# Remotuino-v2.net
KiCad netlist of a schematic drawn in EAGLE
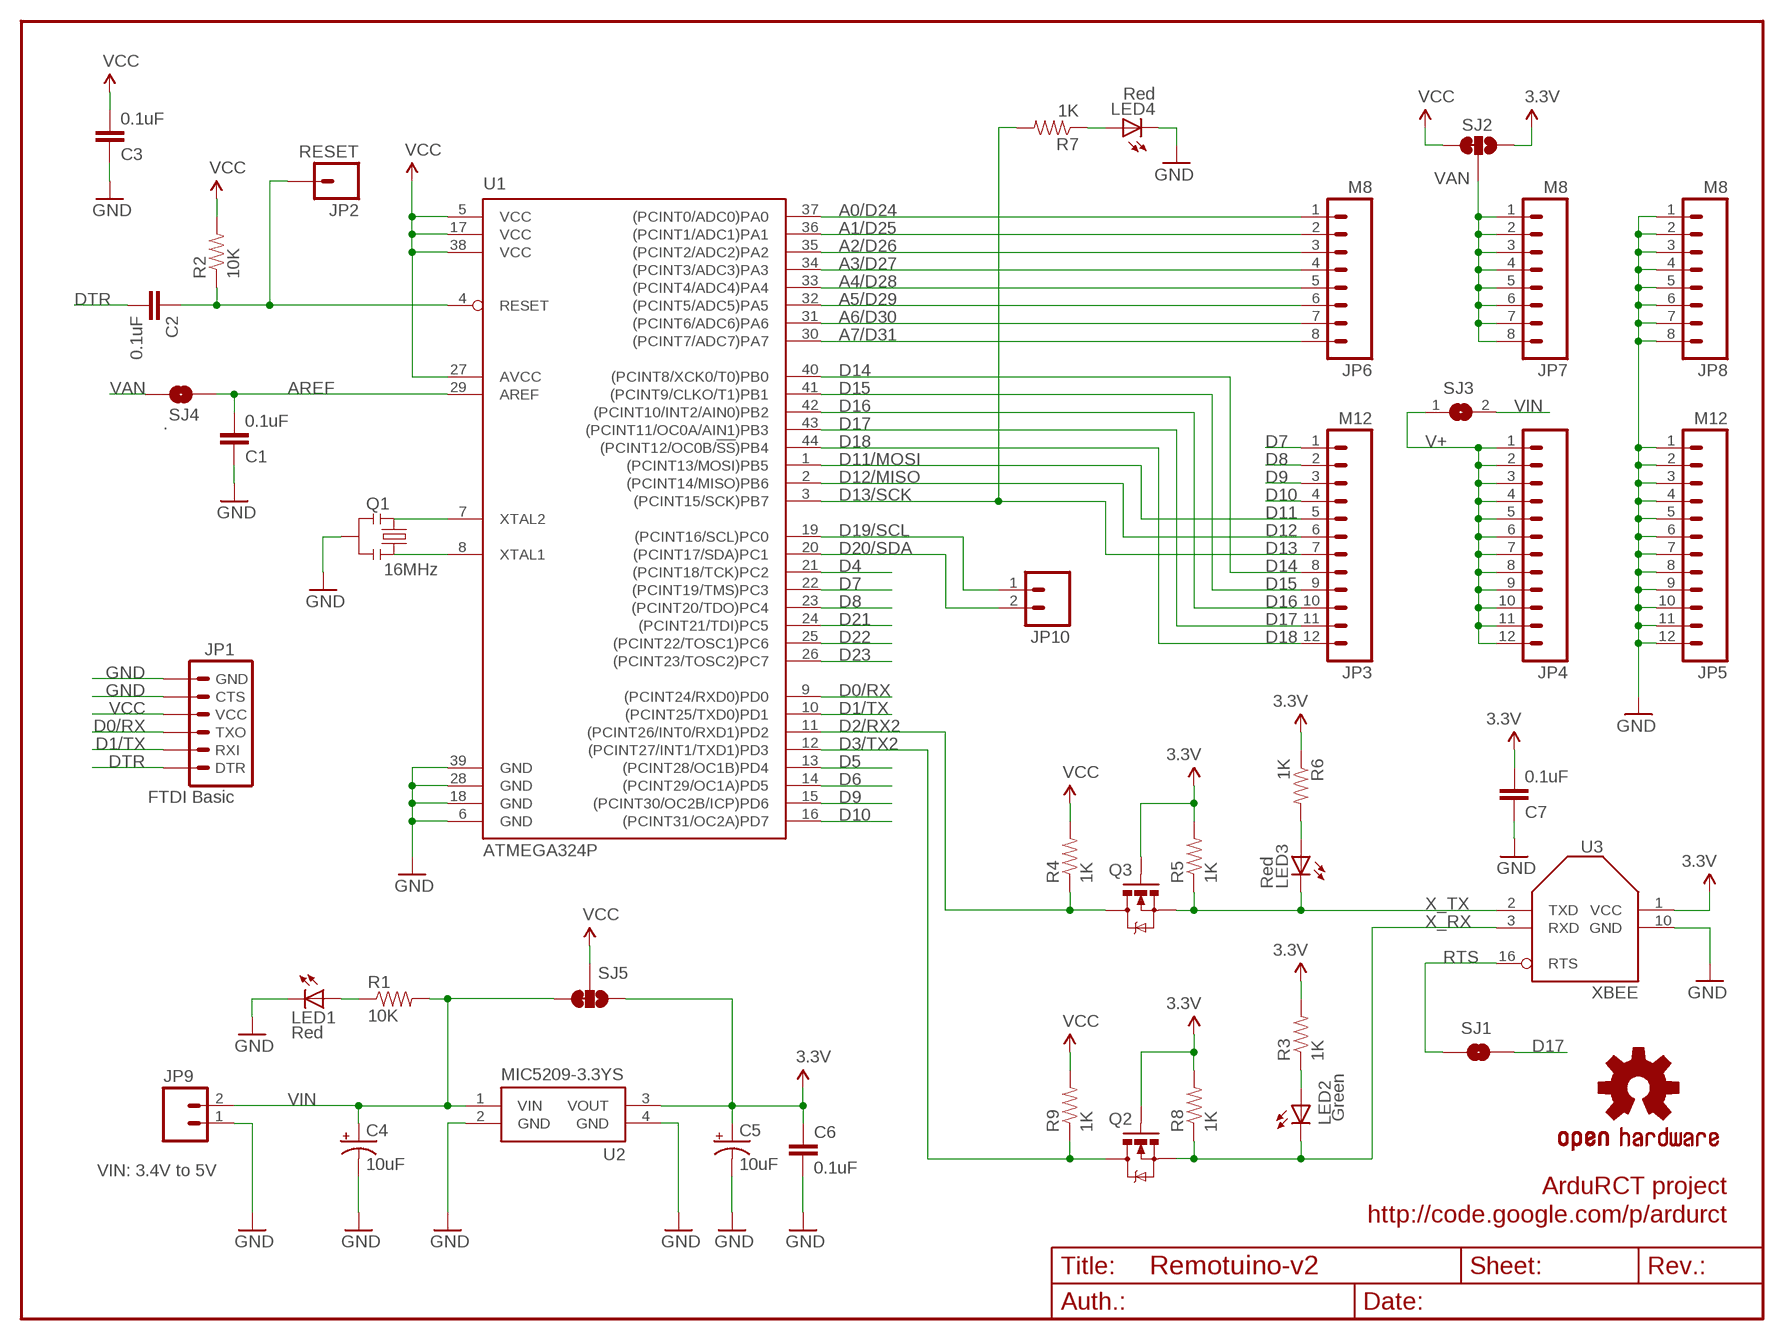
[diagram p0: schematic, sheet 1]

(export (version "E")
  (design (tool "Eeschema 10.0.6"))
  (components
    (comp (ref "C1")
      (value "0.1uF")
      (footprint "eagle-import:0805")
      (libsource (lib "eagle-import") (part "CAP0805"))
    )
    (comp (ref "C2")
      (value "0.1uF")
      (footprint "eagle-import:0805")
      (libsource (lib "eagle-import") (part "CAP0805"))
    )
    (comp (ref "C3")
      (value "0.1uF")
      (footprint "eagle-import:0805")
      (libsource (lib "eagle-import") (part "CAP0805"))
    )
    (comp (ref "C4")
      (value "10uF")
      (footprint "eagle-import:EIA3216")
      (libsource (lib "eagle-import") (part "CAP_POL1206"))
    )
    (comp (ref "C5")
      (value "10uF")
      (footprint "eagle-import:EIA3216")
      (libsource (lib "eagle-import") (part "CAP_POL1206"))
    )
    (comp (ref "C6")
      (value "0.1uF")
      (footprint "eagle-import:0805")
      (libsource (lib "eagle-import") (part "CAP0805"))
    )
    (comp (ref "C7")
      (value "0.1uF")
      (footprint "eagle-import:0805")
      (libsource (lib "eagle-import") (part "CAP0805"))
    )
    (comp (ref "JP1")
      (value "FTDI Basic")
      (footprint "eagle-import:1X06")
      (libsource (lib "eagle-import") (part "ARDUINO_SERIAL_PROGRAMPTH"))
    )
    (comp (ref "JP2")
      (value "RESET")
      (footprint "eagle-import:1X01")
      (libsource (lib "eagle-import") (part "M01PTH"))
    )
    (comp (ref "JP3")
      (value "M12")
      (footprint "eagle-import:1X12")
      (libsource (lib "eagle-import") (part "M12PTH"))
    )
    (comp (ref "JP4")
      (value "M12PTH")
      (footprint "eagle-import:1X12")
      (libsource (lib "eagle-import") (part "M12PTH"))
    )
    (comp (ref "JP5")
      (value "M12")
      (footprint "eagle-import:1X12")
      (libsource (lib "eagle-import") (part "M12PTH"))
    )
    (comp (ref "JP6")
      (value "M8")
      (footprint "eagle-import:1X08")
      (libsource (lib "eagle-import") (part "M08"))
    )
    (comp (ref "JP7")
      (value "M8")
      (footprint "eagle-import:1X08")
      (libsource (lib "eagle-import") (part "M08"))
    )
    (comp (ref "JP8")
      (value "M8")
      (footprint "eagle-import:1X08")
      (libsource (lib "eagle-import") (part "M08"))
    )
    (comp (ref "JP9")
      (value "M02L")
      (footprint "eagle-import:1X2_LONGPAD")
      (libsource (lib "eagle-import") (part "M02L"))
    )
    (comp (ref "JP10")
      (value "M02")
      (footprint "eagle-import:1X02")
      (libsource (lib "eagle-import") (part "M02"))
    )
    (comp (ref "LED1")
      (value "Red")
      (footprint "eagle-import:LED-0805")
      (libsource (lib "eagle-import") (part "LED805"))
    )
    (comp (ref "LED2")
      (value "Green")
      (footprint "eagle-import:LED-0805")
      (libsource (lib "eagle-import") (part "LED805"))
    )
    (comp (ref "LED3")
      (value "Red")
      (footprint "eagle-import:LED-0805")
      (libsource (lib "eagle-import") (part "LED805"))
    )
    (comp (ref "LED4")
      (value "Red")
      (footprint "eagle-import:LED-0805")
      (libsource (lib "eagle-import") (part "LED805"))
    )
    (comp (ref "Q1")
      (value "16MHz")
      (footprint "eagle-import:RESONATOR-SMD")
      (libsource (lib "eagle-import") (part "RESONATORSMD"))
    )
    (comp (ref "Q2")
      (value "BSS138")
      (footprint "eagle-import:SOT23-3")
      (libsource (lib "eagle-import") (part "MOSFET-NCHANNELSMD"))
    )
    (comp (ref "Q3")
      (value "BSS138")
      (footprint "eagle-import:SOT23-3")
      (libsource (lib "eagle-import") (part "MOSFET-NCHANNELSMD"))
    )
    (comp (ref "R1")
      (value "10K")
      (footprint "eagle-import:0805")
      (libsource (lib "eagle-import") (part "RESISTOR0805-RES"))
    )
    (comp (ref "R2")
      (value "10K")
      (footprint "eagle-import:0805")
      (libsource (lib "eagle-import") (part "RESISTOR0805-RES"))
    )
    (comp (ref "R3")
      (value "1K")
      (footprint "eagle-import:0805")
      (libsource (lib "eagle-import") (part "RESISTOR0805-RES"))
    )
    (comp (ref "R4")
      (value "1K")
      (footprint "eagle-import:0805")
      (libsource (lib "eagle-import") (part "RESISTOR0805-RES"))
    )
    (comp (ref "R5")
      (value "1K")
      (footprint "eagle-import:0805")
      (libsource (lib "eagle-import") (part "RESISTOR0805-RES"))
    )
    (comp (ref "R6")
      (value "1K")
      (footprint "eagle-import:0805")
      (libsource (lib "eagle-import") (part "RESISTOR0805-RES"))
    )
    (comp (ref "R7")
      (value "1K")
      (footprint "eagle-import:0805")
      (libsource (lib "eagle-import") (part "RESISTOR0805-RES"))
    )
    (comp (ref "R8")
      (value "1K")
      (footprint "eagle-import:0805")
      (libsource (lib "eagle-import") (part "RESISTOR0805-RES"))
    )
    (comp (ref "R9")
      (value "1K")
      (footprint "eagle-import:0805")
      (libsource (lib "eagle-import") (part "RESISTOR0805-RES"))
    )
    (comp (ref "SJ1")
      (value "SOLDERJUMPERNO")
      (footprint "eagle-import:SJ_2S-NO")
      (libsource (lib "eagle-import") (part "SOLDERJUMPERNO"))
    )
    (comp (ref "SJ2")
      (value "SJ_2WAYS_1-2W")
      (footprint "eagle-import:SJ_2WAYS_1-2")
      (libsource (lib "eagle-import") (part "SJ_2WAYS_1-2W"))
    )
    (comp (ref "SJ3") (value "SJ") (footprint "eagle-import:SJ") (libsource (lib "eagle-import") (part "SJ")))
    (comp (ref "SJ4")
      (value ".")
      (footprint "eagle-import:SJ_2S-TRACE")
      (libsource (lib "eagle-import") (part "SOLDERJUMPERTRACE"))
    )
    (comp (ref "SJ5")
      (value "SJ_2WAYS_1-2W")
      (footprint "eagle-import:SJ_2WAYS_1-2")
      (libsource (lib "eagle-import") (part "SJ_2WAYS_1-2W"))
    )
    (comp (ref "U$2")
      (value "OSHW-LOGOS")
      (footprint "eagle-import:OSHW-LOGO-S")
      (libsource (lib "eagle-import") (part "OSHW-LOGOS"))
    )
    (comp (ref "U1")
      (value "ATMEGA324P")
      (footprint "eagle-import:TQFP44")
      (libsource (lib "eagle-import") (part "ATMEGA324A"))
    )
    (comp (ref "U2")
      (value "MIC5209-3.3YS")
      (footprint "eagle-import:SOT223")
      (libsource (lib "eagle-import") (part "MIC5209"))
    )
    (comp (ref "U3")
      (value "XBEE")
      (footprint "eagle-import:XBEE-MIN")
      (libsource (lib "eagle-import") (part "XBEE-SIMPLE"))
    )
  )
  (nets
    (net (code "1") (name "/A0{slash}D24") (class "Default")
      (node (ref "JP6") (pin "1") (pinfunction "1_1") (pintype "passive"))
      (node (ref "U1") (pin "37") (pinfunction "(PCINT0/ADC0)PA0_37") (pintype "bidirectional"))
    )
    (net (code "2") (name "/A1{slash}D25") (class "Default")
      (node (ref "JP6") (pin "2") (pinfunction "2_2") (pintype "passive"))
      (node (ref "U1") (pin "36") (pinfunction "(PCINT1/ADC1)PA1_36") (pintype "bidirectional"))
    )
    (net (code "3") (name "/A2{slash}D26") (class "Default")
      (node (ref "JP6") (pin "3") (pinfunction "3_3") (pintype "passive"))
      (node (ref "U1") (pin "35") (pinfunction "(PCINT2/ADC2)PA2_35") (pintype "bidirectional"))
    )
    (net (code "4") (name "/A3{slash}D27") (class "Default")
      (node (ref "JP6") (pin "4") (pinfunction "4_4") (pintype "passive"))
      (node (ref "U1") (pin "34") (pinfunction "(PCINT3/ADC3)PA3_34") (pintype "bidirectional"))
    )
    (net (code "5") (name "/A4{slash}D28") (class "Default")
      (node (ref "JP6") (pin "5") (pinfunction "5_5") (pintype "passive"))
      (node (ref "U1") (pin "33") (pinfunction "(PCINT4/ADC4)PA4_33") (pintype "bidirectional"))
    )
    (net (code "6") (name "/A5{slash}D29") (class "Default")
      (node (ref "JP6") (pin "6") (pinfunction "6_6") (pintype "passive"))
      (node (ref "U1") (pin "32") (pinfunction "(PCINT5/ADC5)PA5_32") (pintype "bidirectional"))
    )
    (net (code "7") (name "/A6{slash}D30") (class "Default")
      (node (ref "JP6") (pin "7") (pinfunction "7_7") (pintype "passive"))
      (node (ref "U1") (pin "31") (pinfunction "(PCINT6/ADC6)PA6_31") (pintype "bidirectional"))
    )
    (net (code "8") (name "/A7{slash}D31") (class "Default")
      (node (ref "JP6") (pin "8") (pinfunction "8_8") (pintype "passive"))
      (node (ref "U1") (pin "30") (pinfunction "(PCINT7/ADC7)PA7_30") (pintype "bidirectional"))
    )
    (net (code "9") (name "/AREF") (class "Default")
      (node (ref "C1") (pin "2") (pinfunction "2_2") (pintype "passive"))
      (node (ref "SJ4") (pin "2") (pinfunction "2_2") (pintype "passive"))
      (node (ref "U1") (pin "29") (pinfunction "AREF_29") (pintype "passive"))
    )
    (net (code "10") (name "/D0{slash}RX") (class "Default")
      (node (ref "JP1") (pin "3") (pinfunction "TXO_3") (pintype "passive"))
      (node (ref "U1") (pin "9") (pinfunction "(PCINT24/RXD0)PD0_9") (pintype "bidirectional"))
    )
    (net (code "11") (name "/D1{slash}TX") (class "Default")
      (node (ref "JP1") (pin "2") (pinfunction "RXI_2") (pintype "passive"))
      (node (ref "U1") (pin "10") (pinfunction "(PCINT25/TXD0)PD1_10") (pintype "bidirectional"))
    )
    (net (code "12") (name "/D2{slash}RX2") (class "Default")
      (node (ref "Q3") (pin "3") (pinfunction "D_3") (pintype "passive"))
      (node (ref "R4") (pin "1") (pinfunction "1_1") (pintype "passive"))
      (node (ref "U1") (pin "11") (pinfunction "(PCINT26/INT0/RXD1)PD2_11") (pintype "bidirectional"))
    )
    (net (code "13") (name "/D3{slash}TX2") (class "Default")
      (node (ref "Q2") (pin "3") (pinfunction "D_3") (pintype "passive"))
      (node (ref "R9") (pin "1") (pinfunction "1_1") (pintype "passive"))
      (node (ref "U1") (pin "12") (pinfunction "(PCINT27/INT1/TXD1)PD3_12") (pintype "bidirectional"))
    )
    (net (code "14") (name "/D4") (class "Default")
      (node (ref "U1") (pin "21") (pinfunction "(PCINT18/TCK)PC2_21") (pintype "output"))
    )
    (net (code "15") (name "/D5") (class "Default")
      (node (ref "U1") (pin "13") (pinfunction "(PCINT28/OC1B)PD4_13") (pintype "bidirectional"))
    )
    (net (code "16") (name "/D6") (class "Default")
      (node (ref "U1") (pin "14") (pinfunction "(PCINT29/OC1A)PD5_14") (pintype "bidirectional"))
    )
    (net (code "17") (name "/D7") (class "Default")
      (node (ref "JP3") (pin "1") (pinfunction "1_1") (pintype "passive"))
      (node (ref "U1") (pin "22") (pinfunction "(PCINT19/TMS)PC3_22") (pintype "output"))
    )
    (net (code "18") (name "/D8") (class "Default")
      (node (ref "JP3") (pin "2") (pinfunction "2_2") (pintype "passive"))
      (node (ref "U1") (pin "23") (pinfunction "(PCINT20/TDO)PC4_23") (pintype "output"))
    )
    (net (code "19") (name "/D9") (class "Default")
      (node (ref "JP3") (pin "3") (pinfunction "3_3") (pintype "passive"))
      (node (ref "U1") (pin "15") (pinfunction "(PCINT30/OC2B/ICP)PD6_15") (pintype "bidirectional"))
    )
    (net (code "20") (name "/D10") (class "Default")
      (node (ref "JP3") (pin "4") (pinfunction "4_4") (pintype "passive"))
      (node (ref "U1") (pin "16") (pinfunction "(PCINT31/OC2A)PD7_16") (pintype "bidirectional"))
    )
    (net (code "21") (name "/D11{slash}MOSI") (class "Default")
      (node (ref "JP3") (pin "5") (pinfunction "5_5") (pintype "passive"))
      (node (ref "U1") (pin "1") (pinfunction "(PCINT13/MOSI)PB5_1") (pintype "bidirectional"))
    )
    (net (code "22") (name "/D12{slash}MISO") (class "Default")
      (node (ref "JP3") (pin "6") (pinfunction "6_6") (pintype "passive"))
      (node (ref "U1") (pin "2") (pinfunction "(PCINT14/MISO)PB6_2") (pintype "bidirectional"))
    )
    (net (code "23") (name "/D13{slash}SCK") (class "Default")
      (node (ref "JP3") (pin "7") (pinfunction "7_7") (pintype "passive"))
      (node (ref "R7") (pin "2") (pinfunction "2_2") (pintype "passive"))
      (node (ref "U1") (pin "3") (pinfunction "(PCINT15/SCK)PB7_3") (pintype "bidirectional"))
    )
    (net (code "24") (name "/D14") (class "Default")
      (node (ref "JP3") (pin "8") (pinfunction "8_8") (pintype "passive"))
      (node (ref "U1") (pin "40") (pinfunction "(PCINT8/XCK0/T0)PB0_40") (pintype "bidirectional"))
    )
    (net (code "25") (name "/D15") (class "Default")
      (node (ref "JP3") (pin "9") (pinfunction "9_9") (pintype "passive"))
      (node (ref "U1") (pin "41") (pinfunction "(PCINT9/CLKO/T1)PB1_41") (pintype "bidirectional"))
    )
    (net (code "26") (name "/D16") (class "Default")
      (node (ref "JP3") (pin "10") (pinfunction "10_10") (pintype "passive"))
      (node (ref "U1") (pin "42") (pinfunction "(PCINT10/INT2/AIN0)PB2_42") (pintype "bidirectional"))
    )
    (net (code "27") (name "/D17") (class "Default")
      (node (ref "JP3") (pin "11") (pinfunction "11_11") (pintype "passive"))
      (node (ref "SJ1") (pin "2") (pinfunction "2_2") (pintype "passive"))
      (node (ref "U1") (pin "43") (pinfunction "(PCINT11/OC0A/AIN1)PB3_43") (pintype "bidirectional"))
    )
    (net (code "28") (name "/D18") (class "Default")
      (node (ref "JP3") (pin "12") (pinfunction "12_12") (pintype "passive"))
      (node (ref "U1") (pin "44") (pinfunction "(PCINT12/OC0B/~{SS})PB4_44") (pintype "bidirectional"))
    )
    (net (code "29") (name "/D19{slash}SCL") (class "Default")
      (node (ref "JP10") (pin "1") (pinfunction "1_1") (pintype "passive"))
      (node (ref "U1") (pin "19") (pinfunction "(PCINT16/SCL)PC0_19") (pintype "output"))
    )
    (net (code "30") (name "/D20{slash}SDA") (class "Default")
      (node (ref "JP10") (pin "2") (pinfunction "2_2") (pintype "passive"))
      (node (ref "U1") (pin "20") (pinfunction "(PCINT17/SDA)PC1_20") (pintype "output"))
    )
    (net (code "31") (name "/D21") (class "Default")
      (node (ref "U1") (pin "24") (pinfunction "(PCINT21/TDI)PC5_24") (pintype "output"))
    )
    (net (code "32") (name "/D22") (class "Default")
      (node (ref "U1") (pin "25") (pinfunction "(PCINT22/TOSC1)PC6_25") (pintype "output"))
    )
    (net (code "33") (name "/D23") (class "Default")
      (node (ref "U1") (pin "26") (pinfunction "(PCINT23/TOSC2)PC7_26") (pintype "output"))
    )
    (net (code "34") (name "/DTR") (class "Default")
      (node (ref "C2") (pin "2") (pinfunction "2_2") (pintype "passive"))
      (node (ref "JP1") (pin "1") (pinfunction "DTR_1") (pintype "passive"))
    )
    (net (code "35") (name "/RTS") (class "Default")
      (node (ref "SJ1") (pin "1") (pinfunction "1_1") (pintype "passive"))
      (node (ref "U3") (pin "16") (pinfunction "RTS_16") (pintype "bidirectional"))
    )
    (net (code "36") (name "/V+") (class "Default")
      (node (ref "JP4") (pin "1") (pinfunction "1_1") (pintype "passive"))
      (node (ref "JP4") (pin "10") (pinfunction "10_10") (pintype "passive"))
      (node (ref "JP4") (pin "11") (pinfunction "11_11") (pintype "passive"))
      (node (ref "JP4") (pin "12") (pinfunction "12_12") (pintype "passive"))
      (node (ref "JP4") (pin "2") (pinfunction "2_2") (pintype "passive"))
      (node (ref "JP4") (pin "3") (pinfunction "3_3") (pintype "passive"))
      (node (ref "JP4") (pin "4") (pinfunction "4_4") (pintype "passive"))
      (node (ref "JP4") (pin "5") (pinfunction "5_5") (pintype "passive"))
      (node (ref "JP4") (pin "6") (pinfunction "6_6") (pintype "passive"))
      (node (ref "JP4") (pin "7") (pinfunction "7_7") (pintype "passive"))
      (node (ref "JP4") (pin "8") (pinfunction "8_8") (pintype "passive"))
      (node (ref "JP4") (pin "9") (pinfunction "9_9") (pintype "passive"))
      (node (ref "SJ3") (pin "1") (pinfunction "1_1") (pintype "passive"))
    )
    (net (code "37") (name "/VAN") (class "Default")
      (node (ref "JP7") (pin "1") (pinfunction "1_1") (pintype "passive"))
      (node (ref "JP7") (pin "2") (pinfunction "2_2") (pintype "passive"))
      (node (ref "JP7") (pin "3") (pinfunction "3_3") (pintype "passive"))
      (node (ref "JP7") (pin "4") (pinfunction "4_4") (pintype "passive"))
      (node (ref "JP7") (pin "5") (pinfunction "5_5") (pintype "passive"))
      (node (ref "JP7") (pin "6") (pinfunction "6_6") (pintype "passive"))
      (node (ref "JP7") (pin "7") (pinfunction "7_7") (pintype "passive"))
      (node (ref "JP7") (pin "8") (pinfunction "8_8") (pintype "passive"))
      (node (ref "SJ2") (pin "2") (pinfunction "2_2") (pintype "passive"))
      (node (ref "SJ4") (pin "1") (pinfunction "1_1") (pintype "passive"))
    )
    (net (code "38") (name "/VIN") (class "Default")
      (node (ref "C4") (pin "A") (pinfunction "+_A") (pintype "passive"))
      (node (ref "JP9") (pin "2") (pinfunction "2_2") (pintype "passive"))
      (node (ref "R1") (pin "2") (pinfunction "2_2") (pintype "passive"))
      (node (ref "SJ3") (pin "2") (pinfunction "2_2") (pintype "passive"))
      (node (ref "SJ5") (pin "1") (pinfunction "1_1") (pintype "passive"))
      (node (ref "U2") (pin "1") (pinfunction "VIN_1") (pintype "bidirectional"))
    )
    (net (code "39") (name "/X_RX") (class "Default")
      (node (ref "LED2") (pin "2") (pinfunction "C_2") (pintype "passive"))
      (node (ref "Q2") (pin "2") (pinfunction "S_2") (pintype "passive"))
      (node (ref "R8") (pin "1") (pinfunction "1_1") (pintype "passive"))
      (node (ref "U3") (pin "3") (pinfunction "RXD_3") (pintype "bidirectional"))
    )
    (net (code "40") (name "/X_TX") (class "Default")
      (node (ref "LED3") (pin "2") (pinfunction "C_2") (pintype "passive"))
      (node (ref "Q3") (pin "2") (pinfunction "S_2") (pintype "passive"))
      (node (ref "R5") (pin "1") (pinfunction "1_1") (pintype "passive"))
      (node (ref "U3") (pin "2") (pinfunction "TXD_2") (pintype "bidirectional"))
    )
    (net (code "41") (name "3.3V") (class "Default")
      (node (ref "C5") (pin "A") (pinfunction "+_A") (pintype "passive"))
      (node (ref "C6") (pin "1") (pinfunction "1_1") (pintype "passive"))
      (node (ref "C7") (pin "2") (pinfunction "2_2") (pintype "passive"))
      (node (ref "Q2") (pin "1") (pinfunction "G_1") (pintype "passive"))
      (node (ref "Q3") (pin "1") (pinfunction "G_1") (pintype "passive"))
      (node (ref "R3") (pin "2") (pinfunction "2_2") (pintype "passive"))
      (node (ref "R5") (pin "2") (pinfunction "2_2") (pintype "passive"))
      (node (ref "R6") (pin "1") (pinfunction "1_1") (pintype "passive"))
      (node (ref "R8") (pin "2") (pinfunction "2_2") (pintype "passive"))
      (node (ref "SJ2") (pin "3") (pinfunction "3_3") (pintype "passive"))
      (node (ref "SJ5") (pin "3") (pinfunction "3_3") (pintype "passive"))
      (node (ref "U2") (pin "3") (pinfunction "VOUT_3") (pintype "bidirectional"))
      (node (ref "U3") (pin "1") (pinfunction "VCC_1") (pintype "bidirectional"))
    )
    (net (code "42") (name "GND") (class "Default")
      (node (ref "C1") (pin "1") (pinfunction "1_1") (pintype "passive"))
      (node (ref "C3") (pin "1") (pinfunction "1_1") (pintype "passive"))
      (node (ref "C4") (pin "C") (pinfunction "-_C") (pintype "passive"))
      (node (ref "C5") (pin "C") (pinfunction "-_C") (pintype "passive"))
      (node (ref "C6") (pin "2") (pinfunction "2_2") (pintype "passive"))
      (node (ref "C7") (pin "1") (pinfunction "1_1") (pintype "passive"))
      (node (ref "JP1") (pin "5") (pinfunction "CTS_5") (pintype "passive"))
      (node (ref "JP1") (pin "6") (pinfunction "GND_6") (pintype "passive"))
      (node (ref "JP5") (pin "1") (pinfunction "1_1") (pintype "passive"))
      (node (ref "JP5") (pin "10") (pinfunction "10_10") (pintype "passive"))
      (node (ref "JP5") (pin "11") (pinfunction "11_11") (pintype "passive"))
      (node (ref "JP5") (pin "12") (pinfunction "12_12") (pintype "passive"))
      (node (ref "JP5") (pin "2") (pinfunction "2_2") (pintype "passive"))
      (node (ref "JP5") (pin "3") (pinfunction "3_3") (pintype "passive"))
      (node (ref "JP5") (pin "4") (pinfunction "4_4") (pintype "passive"))
      (node (ref "JP5") (pin "5") (pinfunction "5_5") (pintype "passive"))
      (node (ref "JP5") (pin "6") (pinfunction "6_6") (pintype "passive"))
      (node (ref "JP5") (pin "7") (pinfunction "7_7") (pintype "passive"))
      (node (ref "JP5") (pin "8") (pinfunction "8_8") (pintype "passive"))
      (node (ref "JP5") (pin "9") (pinfunction "9_9") (pintype "passive"))
      (node (ref "JP8") (pin "1") (pinfunction "1_1") (pintype "passive"))
      (node (ref "JP8") (pin "2") (pinfunction "2_2") (pintype "passive"))
      (node (ref "JP8") (pin "3") (pinfunction "3_3") (pintype "passive"))
      (node (ref "JP8") (pin "4") (pinfunction "4_4") (pintype "passive"))
      (node (ref "JP8") (pin "5") (pinfunction "5_5") (pintype "passive"))
      (node (ref "JP8") (pin "6") (pinfunction "6_6") (pintype "passive"))
      (node (ref "JP8") (pin "7") (pinfunction "7_7") (pintype "passive"))
      (node (ref "JP8") (pin "8") (pinfunction "8_8") (pintype "passive"))
      (node (ref "JP9") (pin "1") (pinfunction "1_1") (pintype "passive"))
      (node (ref "LED1") (pin "2") (pinfunction "C_2") (pintype "passive"))
      (node (ref "LED4") (pin "2") (pinfunction "C_2") (pintype "passive"))
      (node (ref "Q1") (pin "2") (pinfunction "2_2") (pintype "passive"))
      (node (ref "U1") (pin "18") (pinfunction "GND_18") (pintype "power_in"))
      (node (ref "U1") (pin "28") (pinfunction "GND_28") (pintype "power_in"))
      (node (ref "U1") (pin "39") (pinfunction "GND_39") (pintype "power_in"))
      (node (ref "U1") (pin "6") (pinfunction "GND_6") (pintype "power_in"))
      (node (ref "U2") (pin "2") (pinfunction "GND_2") (pintype "bidirectional"))
      (node (ref "U2") (pin "4") (pinfunction "GND_4") (pintype "bidirectional"))
      (node (ref "U3") (pin "10") (pinfunction "GND_10") (pintype "bidirectional"))
    )
    (net (code "43") (name "Net-(LED1-A)") (class "Default")
      (node (ref "LED1") (pin "1") (pinfunction "A_1") (pintype "passive"))
      (node (ref "R1") (pin "1") (pinfunction "1_1") (pintype "passive"))
    )
    (net (code "44") (name "Net-(LED2-A)") (class "Default")
      (node (ref "LED2") (pin "1") (pinfunction "A_1") (pintype "passive"))
      (node (ref "R3") (pin "1") (pinfunction "1_1") (pintype "passive"))
    )
    (net (code "45") (name "Net-(LED3-A)") (class "Default")
      (node (ref "LED3") (pin "1") (pinfunction "A_1") (pintype "passive"))
      (node (ref "R6") (pin "2") (pinfunction "2_2") (pintype "passive"))
    )
    (net (code "46") (name "Net-(LED4-A)") (class "Default")
      (node (ref "LED4") (pin "1") (pinfunction "A_1") (pintype "passive"))
      (node (ref "R7") (pin "1") (pinfunction "1_1") (pintype "passive"))
    )
    (net (code "47") (name "Net-(U1-RESET)") (class "Default")
      (node (ref "C2") (pin "1") (pinfunction "1_1") (pintype "passive"))
      (node (ref "JP2") (pin "1") (pinfunction "1_1") (pintype "passive"))
      (node (ref "R2") (pin "1") (pinfunction "1_1") (pintype "passive"))
      (node (ref "U1") (pin "4") (pinfunction "RESET_4") (pintype "input"))
    )
    (net (code "48") (name "Net-(U1-XTAL1)") (class "Default")
      (node (ref "Q1") (pin "1") (pinfunction "1_1") (pintype "passive"))
      (node (ref "U1") (pin "8") (pinfunction "XTAL1_8") (pintype "bidirectional"))
    )
    (net (code "49") (name "Net-(U1-XTAL2)") (class "Default")
      (node (ref "Q1") (pin "3") (pinfunction "3_3") (pintype "passive"))
      (node (ref "U1") (pin "7") (pinfunction "XTAL2_7") (pintype "bidirectional"))
    )
    (net (code "50") (name "VCC") (class "Default")
      (node (ref "C3") (pin "2") (pinfunction "2_2") (pintype "passive"))
      (node (ref "JP1") (pin "4") (pinfunction "VCC_4") (pintype "passive"))
      (node (ref "R2") (pin "2") (pinfunction "2_2") (pintype "passive"))
      (node (ref "R4") (pin "2") (pinfunction "2_2") (pintype "passive"))
      (node (ref "R9") (pin "2") (pinfunction "2_2") (pintype "passive"))
      (node (ref "SJ2") (pin "1") (pinfunction "1_1") (pintype "passive"))
      (node (ref "SJ5") (pin "2") (pinfunction "2_2") (pintype "passive"))
      (node (ref "U1") (pin "17") (pinfunction "VCC_17") (pintype "power_in"))
      (node (ref "U1") (pin "27") (pinfunction "AVCC_27") (pintype "power_in"))
      (node (ref "U1") (pin "38") (pinfunction "VCC_38") (pintype "power_in"))
      (node (ref "U1") (pin "5") (pinfunction "VCC_5") (pintype "power_in"))
    )
  )
)
